# timbangan_bayi.net
KiCad netlist of a schematic drawn in EAGLE
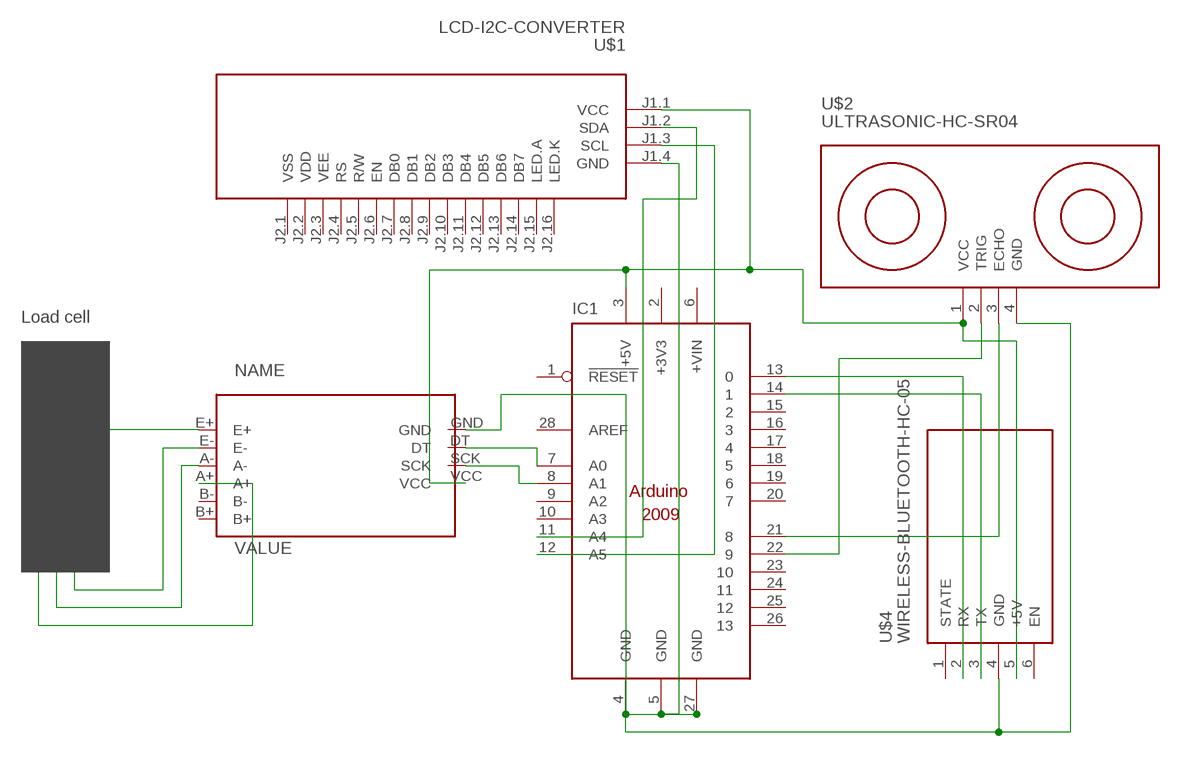
[diagram p0: schematic, sheet 1]

(export (version "E")
  (design (tool "Eeschema 10.0.6"))
  (components
    (comp (ref "IC1")
      (value "ARDUINO2009_10")
      (footprint "eagle-import:ARDUINO2009")
      (libsource (lib "eagle-import") (part "ARDUINO2009_10"))
    )
    (comp (ref "U$1")
      (value "LCD-I2C-CONVERTER")
      (footprint "eagle-import:LCD-I2C-CONVERTER")
      (libsource (lib "eagle-import") (part "LCD-I2C-CONVERTER"))
    )
    (comp (ref "U$2")
      (value "ULTRASONIC-HC-SR04")
      (footprint "eagle-import:ULTRASONIC-HC-SR04")
      (libsource (lib "eagle-import") (part "ULTRASONIC-HC-SR04"))
    )
    (comp (ref "U$3")
      (value "HX711A")
      (footprint "eagle-import:HX711")
      (libsource (lib "eagle-import") (part "HX711A"))
    )
    (comp (ref "U$4")
      (value "WIRELESS-BLUETOOTH-HC-05")
      (footprint "eagle-import:WIRELESS-BLUETOOTH-HC-05")
      (libsource (lib "eagle-import") (part "WIRELESS-BLUETOOTH-HC-05"))
    )
  )
  (nets
    (net (code "1") (name "/+3V3") (class "Default")
      (node (ref "IC1") (pin "2") (pinfunction "+3V3_2") (pintype "power_in"))
    )
    (net (code "2") (name "Net-(IC1-+5V)") (class "Default")
      (node (ref "IC1") (pin "3") (pinfunction "+5V_3") (pintype "power_in"))
      (node (ref "U$1") (pin "J1.1") (pinfunction "VCC_J1.1") (pintype "power_in"))
      (node (ref "U$2") (pin "1") (pinfunction "VCC_1") (pintype "power_in"))
      (node (ref "U$3") (pin "VCC") (pinfunction "VCC_VCC") (pintype "bidirectional"))
      (node (ref "U$4") (pin "5") (pinfunction "+5V_5") (pintype "power_in"))
    )
    (net (code "3") (name "Net-(IC1-0)") (class "Default")
      (node (ref "IC1") (pin "13") (pinfunction "0_13") (pintype "bidirectional"))
      (node (ref "U$4") (pin "2") (pinfunction "RX_2") (pintype "bidirectional"))
    )
    (net (code "4") (name "Net-(IC1-1)") (class "Default")
      (node (ref "IC1") (pin "14") (pinfunction "1_14") (pintype "bidirectional"))
      (node (ref "U$4") (pin "3") (pinfunction "TX_3") (pintype "bidirectional"))
    )
    (net (code "5") (name "Net-(IC1-8)") (class "Default")
      (node (ref "IC1") (pin "21") (pinfunction "8_21") (pintype "bidirectional"))
      (node (ref "U$2") (pin "3") (pinfunction "ECHO_3") (pintype "output"))
    )
    (net (code "6") (name "Net-(IC1-9)") (class "Default")
      (node (ref "IC1") (pin "22") (pinfunction "9_22") (pintype "bidirectional"))
      (node (ref "U$2") (pin "2") (pinfunction "TRIG_2") (pintype "input"))
    )
    (net (code "7") (name "Net-(IC1-A0)") (class "Default")
      (node (ref "IC1") (pin "7") (pinfunction "A0_7") (pintype "bidirectional"))
      (node (ref "U$3") (pin "DT") (pinfunction "DT_DT") (pintype "bidirectional"))
    )
    (net (code "8") (name "Net-(IC1-A1)") (class "Default")
      (node (ref "IC1") (pin "8") (pinfunction "A1_8") (pintype "bidirectional"))
      (node (ref "U$3") (pin "SCK") (pinfunction "SCK_SCK") (pintype "bidirectional"))
    )
    (net (code "9") (name "Net-(IC1-A4)") (class "Default")
      (node (ref "IC1") (pin "11") (pinfunction "A4_11") (pintype "bidirectional"))
      (node (ref "U$1") (pin "J1.2") (pinfunction "SDA_J1.2") (pintype "bidirectional"))
    )
    (net (code "10") (name "Net-(IC1-A5)") (class "Default")
      (node (ref "IC1") (pin "12") (pinfunction "A5_12") (pintype "bidirectional"))
      (node (ref "U$1") (pin "J1.3") (pinfunction "SCL_J1.3") (pintype "bidirectional"))
    )
    (net (code "11") (name "Net-(U$1-GND)") (class "Default")
      (node (ref "IC1") (pin "27") (pinfunction "GND_27") (pintype "power_in"))
      (node (ref "IC1") (pin "4") (pinfunction "GND_4") (pintype "power_in"))
      (node (ref "IC1") (pin "5") (pinfunction "GND_5") (pintype "power_in"))
      (node (ref "U$1") (pin "J1.4") (pinfunction "GND_J1.4") (pintype "power_in"))
      (node (ref "U$2") (pin "4") (pinfunction "GND_4") (pintype "power_in"))
      (node (ref "U$3") (pin "GND") (pinfunction "GND_GND") (pintype "bidirectional"))
      (node (ref "U$4") (pin "4") (pinfunction "GND_4") (pintype "power_in"))
    )
    (net (code "12") (name "unconnected-(IC1-+VIN-Pad6)") (class "Default")
      (node (ref "IC1") (pin "6") (pinfunction "+VIN_6") (pintype "bidirectional"))
    )
    (net (code "13") (name "unconnected-(IC1-2-Pad15)") (class "Default")
      (node (ref "IC1") (pin "15") (pinfunction "2_15") (pintype "bidirectional"))
    )
    (net (code "14") (name "unconnected-(IC1-3-Pad16)") (class "Default")
      (node (ref "IC1") (pin "16") (pinfunction "3_16") (pintype "bidirectional"))
    )
    (net (code "15") (name "unconnected-(IC1-4-Pad17)") (class "Default")
      (node (ref "IC1") (pin "17") (pinfunction "4_17") (pintype "bidirectional"))
    )
    (net (code "16") (name "unconnected-(IC1-5-Pad18)") (class "Default")
      (node (ref "IC1") (pin "18") (pinfunction "5_18") (pintype "bidirectional"))
    )
    (net (code "17") (name "unconnected-(IC1-6-Pad19)") (class "Default")
      (node (ref "IC1") (pin "19") (pinfunction "6_19") (pintype "bidirectional"))
    )
    (net (code "18") (name "unconnected-(IC1-7-Pad20)") (class "Default")
      (node (ref "IC1") (pin "20") (pinfunction "7_20") (pintype "bidirectional"))
    )
    (net (code "19") (name "unconnected-(IC1-10-Pad23)") (class "Default")
      (node (ref "IC1") (pin "23") (pinfunction "10_23") (pintype "bidirectional"))
    )
    (net (code "20") (name "unconnected-(IC1-11-Pad24)") (class "Default")
      (node (ref "IC1") (pin "24") (pinfunction "11_24") (pintype "bidirectional"))
    )
    (net (code "21") (name "unconnected-(IC1-12-Pad25)") (class "Default")
      (node (ref "IC1") (pin "25") (pinfunction "12_25") (pintype "bidirectional"))
    )
    (net (code "22") (name "unconnected-(IC1-13-Pad26)") (class "Default")
      (node (ref "IC1") (pin "26") (pinfunction "13_26") (pintype "bidirectional"))
    )
    (net (code "23") (name "unconnected-(IC1-A2-Pad9)") (class "Default")
      (node (ref "IC1") (pin "9") (pinfunction "A2_9") (pintype "bidirectional"))
    )
    (net (code "24") (name "unconnected-(IC1-A3-Pad10)") (class "Default")
      (node (ref "IC1") (pin "10") (pinfunction "A3_10") (pintype "bidirectional"))
    )
    (net (code "25") (name "unconnected-(IC1-AREF-Pad28)") (class "Default")
      (node (ref "IC1") (pin "28") (pinfunction "AREF_28") (pintype "bidirectional"))
    )
    (net (code "26") (name "unconnected-(IC1-~{RESET}-Pad1)") (class "Default")
      (node (ref "IC1") (pin "1") (pinfunction "~{RESET}_1") (pintype "bidirectional"))
    )
    (net (code "27") (name "unconnected-(U$1-DB0-PadJ2.7)") (class "Default")
      (node (ref "U$1") (pin "J2.7") (pinfunction "DB0_J2.7") (pintype "bidirectional"))
    )
    (net (code "28") (name "unconnected-(U$1-DB1-PadJ2.8)") (class "Default")
      (node (ref "U$1") (pin "J2.8") (pinfunction "DB1_J2.8") (pintype "bidirectional"))
    )
    (net (code "29") (name "unconnected-(U$1-DB2-PadJ2.9)") (class "Default")
      (node (ref "U$1") (pin "J2.9") (pinfunction "DB2_J2.9") (pintype "bidirectional"))
    )
    (net (code "30") (name "unconnected-(U$1-DB3-PadJ2.10)") (class "Default")
      (node (ref "U$1") (pin "J2.10") (pinfunction "DB3_J2.10") (pintype "bidirectional"))
    )
    (net (code "31") (name "unconnected-(U$1-DB4-PadJ2.11)") (class "Default")
      (node (ref "U$1") (pin "J2.11") (pinfunction "DB4_J2.11") (pintype "bidirectional"))
    )
    (net (code "32") (name "unconnected-(U$1-DB5-PadJ2.12)") (class "Default")
      (node (ref "U$1") (pin "J2.12") (pinfunction "DB5_J2.12") (pintype "bidirectional"))
    )
    (net (code "33") (name "unconnected-(U$1-DB6-PadJ2.13)") (class "Default")
      (node (ref "U$1") (pin "J2.13") (pinfunction "DB6_J2.13") (pintype "bidirectional"))
    )
    (net (code "34") (name "unconnected-(U$1-DB7-PadJ2.14)") (class "Default")
      (node (ref "U$1") (pin "J2.14") (pinfunction "DB7_J2.14") (pintype "bidirectional"))
    )
    (net (code "35") (name "unconnected-(U$1-EN-PadJ2.6)") (class "Default")
      (node (ref "U$1") (pin "J2.6") (pinfunction "EN_J2.6") (pintype "bidirectional"))
    )
    (net (code "36") (name "unconnected-(U$1-LED.A-PadJ2.15)") (class "Default")
      (node (ref "U$1") (pin "J2.15") (pinfunction "LED.A_J2.15") (pintype "bidirectional"))
    )
    (net (code "37") (name "unconnected-(U$1-LED.K-PadJ2.16)") (class "Default")
      (node (ref "U$1") (pin "J2.16") (pinfunction "LED.K_J2.16") (pintype "bidirectional"))
    )
    (net (code "38") (name "unconnected-(U$1-RS-PadJ2.4)") (class "Default")
      (node (ref "U$1") (pin "J2.4") (pinfunction "RS_J2.4") (pintype "bidirectional"))
    )
    (net (code "39") (name "unconnected-(U$1-R{slash}W-PadJ2.5)") (class "Default")
      (node (ref "U$1") (pin "J2.5") (pinfunction "R/W_J2.5") (pintype "bidirectional"))
    )
    (net (code "40") (name "unconnected-(U$1-VDD-PadJ2.2)") (class "Default")
      (node (ref "U$1") (pin "J2.2") (pinfunction "VDD_J2.2") (pintype "bidirectional"))
    )
    (net (code "41") (name "unconnected-(U$1-VEE-PadJ2.3)") (class "Default")
      (node (ref "U$1") (pin "J2.3") (pinfunction "VEE_J2.3") (pintype "bidirectional"))
    )
    (net (code "42") (name "unconnected-(U$1-VSS-PadJ2.1)") (class "Default")
      (node (ref "U$1") (pin "J2.1") (pinfunction "VSS_J2.1") (pintype "bidirectional"))
    )
    (net (code "43") (name "unconnected-(U$3-PadA+)") (class "Default")
      (node (ref "U$3") (pin "A+") (pinfunction "A+_A+") (pintype "bidirectional"))
    )
    (net (code "44") (name "unconnected-(U$3-PadA-)") (class "Default")
      (node (ref "U$3") (pin "A-") (pinfunction "A-_A-") (pintype "bidirectional"))
    )
    (net (code "45") (name "unconnected-(U$3-PadB+)") (class "Default")
      (node (ref "U$3") (pin "B+") (pinfunction "B+_B+") (pintype "bidirectional"))
    )
    (net (code "46") (name "unconnected-(U$3-PadB-)") (class "Default")
      (node (ref "U$3") (pin "B-") (pinfunction "B-_B-") (pintype "bidirectional"))
    )
    (net (code "47") (name "unconnected-(U$3-PadE+)") (class "Default")
      (node (ref "U$3") (pin "E+") (pinfunction "E+_E+") (pintype "bidirectional"))
    )
    (net (code "48") (name "unconnected-(U$3-PadE-)") (class "Default")
      (node (ref "U$3") (pin "E-") (pinfunction "E-_E-") (pintype "bidirectional"))
    )
    (net (code "49") (name "unconnected-(U$4-EN-Pad6)") (class "Default")
      (node (ref "U$4") (pin "6") (pinfunction "EN_6") (pintype "bidirectional"))
    )
    (net (code "50") (name "unconnected-(U$4-STATE-Pad1)") (class "Default")
      (node (ref "U$4") (pin "1") (pinfunction "STATE_1") (pintype "bidirectional"))
    )
  )
)
